# Power_Board_DCDC19V5.net
KiCad netlist of a schematic drawn in Altium Designer
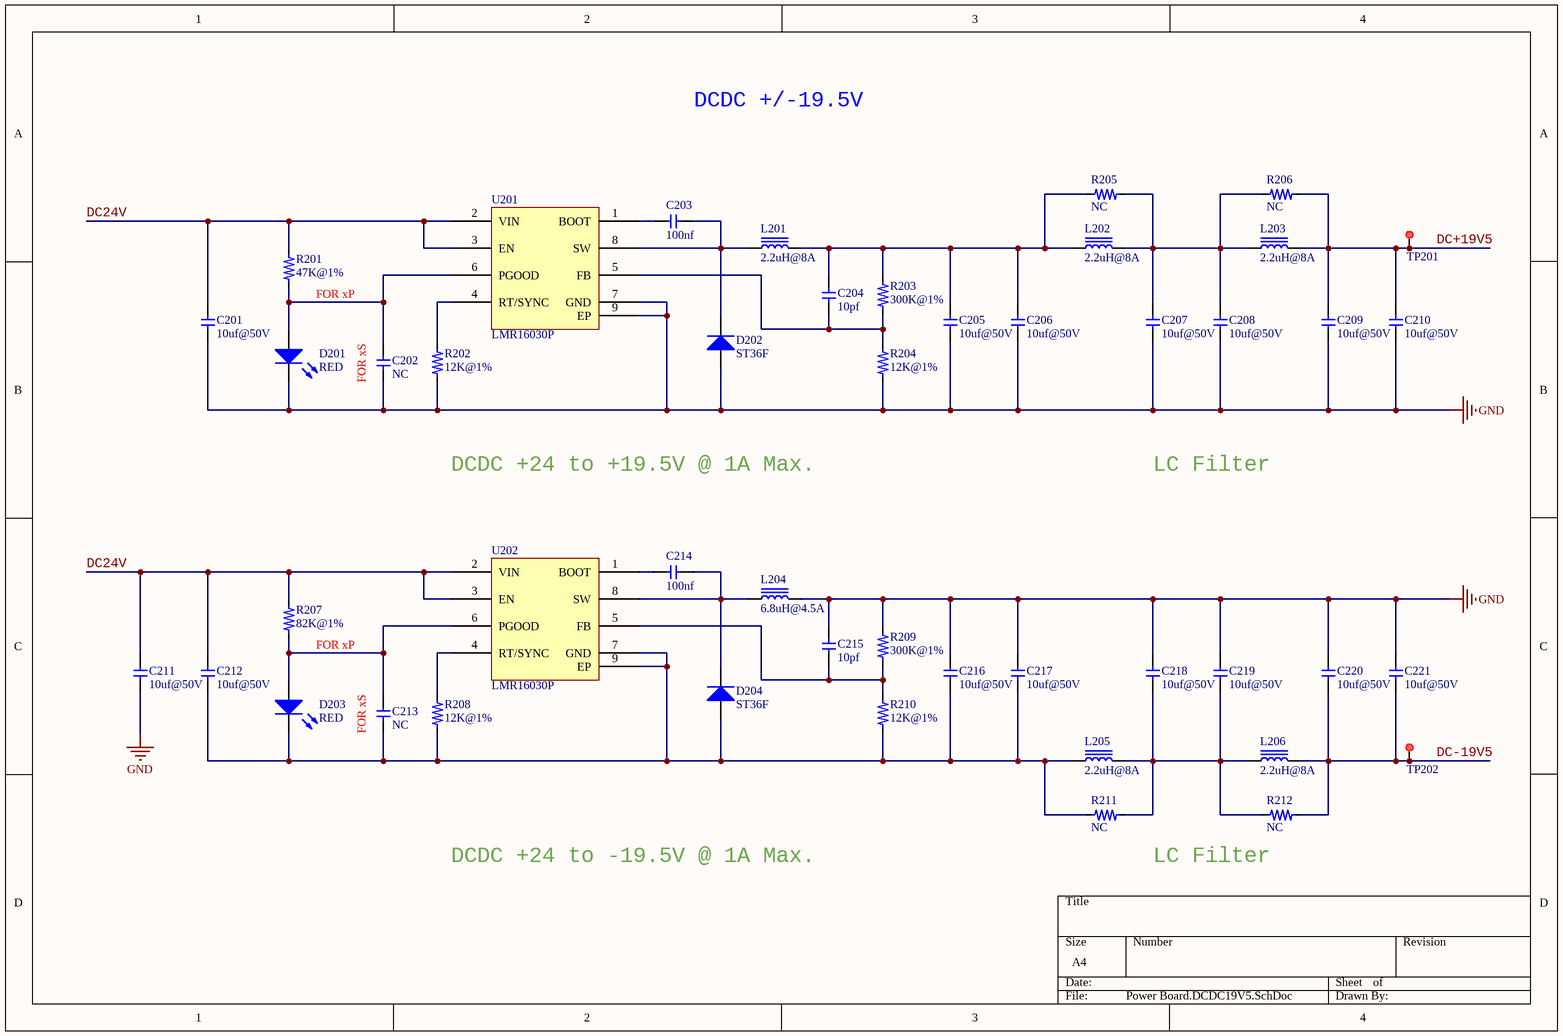
[diagram p0: Power Board.DCDC19V5.SchDoc]

(export (version "E")
  (design (tool "Eeschema 10.0.6"))
  (components
    (comp (ref "C201")
      (value "10uf@50V")
      (footprint "C1206")
      (fields (field (name "Comment") "Cap"))
      (libsource (lib "carrot_lib") (part "Cap"))
    )
    (comp (ref "C202")
      (value "NC")
      (footprint "C0603")
      (fields (field (name "Comment") "Cap"))
      (libsource (lib "carrot_lib") (part "Cap"))
    )
    (comp (ref "C203")
      (value "100nf")
      (footprint "C0603")
      (fields (field (name "Comment") "Cap"))
      (libsource (lib "carrot_lib") (part "Cap"))
    )
    (comp (ref "C204")
      (value "10pf")
      (footprint "C0603")
      (fields (field (name "Comment") "Cap"))
      (libsource (lib "carrot_lib") (part "Cap"))
    )
    (comp (ref "C205")
      (value "10uf@50V")
      (footprint "C1206")
      (fields (field (name "Comment") "Cap"))
      (libsource (lib "carrot_lib") (part "Cap"))
    )
    (comp (ref "C206")
      (value "10uf@50V")
      (footprint "C1206")
      (fields (field (name "Comment") "Cap"))
      (libsource (lib "carrot_lib") (part "Cap"))
    )
    (comp (ref "C207")
      (value "10uf@50V")
      (footprint "C1206")
      (fields (field (name "Comment") "Cap"))
      (libsource (lib "carrot_lib") (part "Cap"))
    )
    (comp (ref "C208")
      (value "10uf@50V")
      (footprint "C1206")
      (fields (field (name "Comment") "Cap"))
      (libsource (lib "carrot_lib") (part "Cap"))
    )
    (comp (ref "C209")
      (value "10uf@50V")
      (footprint "C1206")
      (fields (field (name "Comment") "Cap"))
      (libsource (lib "carrot_lib") (part "Cap"))
    )
    (comp (ref "C210")
      (value "10uf@50V")
      (footprint "C1206")
      (fields (field (name "Comment") "Cap"))
      (libsource (lib "carrot_lib") (part "Cap"))
    )
    (comp (ref "C211")
      (value "10uf@50V")
      (footprint "C1206")
      (fields (field (name "Comment") "Cap"))
      (libsource (lib "carrot_lib") (part "Cap"))
    )
    (comp (ref "C212")
      (value "10uf@50V")
      (footprint "C1206")
      (fields (field (name "Comment") "Cap"))
      (libsource (lib "carrot_lib") (part "Cap"))
    )
    (comp (ref "C213")
      (value "NC")
      (footprint "C0603")
      (fields (field (name "Comment") "Cap"))
      (libsource (lib "carrot_lib") (part "Cap"))
    )
    (comp (ref "C214")
      (value "100nf")
      (footprint "C0603")
      (fields (field (name "Comment") "Cap"))
      (libsource (lib "carrot_lib") (part "Cap"))
    )
    (comp (ref "C215")
      (value "10pf")
      (footprint "C0603")
      (fields (field (name "Comment") "Cap"))
      (libsource (lib "carrot_lib") (part "Cap"))
    )
    (comp (ref "C216")
      (value "10uf@50V")
      (footprint "C1206")
      (fields (field (name "Comment") "Cap"))
      (libsource (lib "carrot_lib") (part "Cap"))
    )
    (comp (ref "C217")
      (value "10uf@50V")
      (footprint "C1206")
      (fields (field (name "Comment") "Cap"))
      (libsource (lib "carrot_lib") (part "Cap"))
    )
    (comp (ref "C218")
      (value "10uf@50V")
      (footprint "C1206")
      (fields (field (name "Comment") "Cap"))
      (libsource (lib "carrot_lib") (part "Cap"))
    )
    (comp (ref "C219")
      (value "10uf@50V")
      (footprint "C1206")
      (fields (field (name "Comment") "Cap"))
      (libsource (lib "carrot_lib") (part "Cap"))
    )
    (comp (ref "C220")
      (value "10uf@50V")
      (footprint "C1206")
      (fields (field (name "Comment") "Cap"))
      (libsource (lib "carrot_lib") (part "Cap"))
    )
    (comp (ref "C221")
      (value "10uf@50V")
      (footprint "C1206")
      (fields (field (name "Comment") "Cap"))
      (libsource (lib "carrot_lib") (part "Cap"))
    )
    (comp (ref "D201")
      (value "RED")
      (footprint "LED0603")
      (fields (field (name "Comment") "LED"))
      (libsource (lib "carrot_lib") (part "LED"))
    )
    (comp (ref "D202")
      (value "ST36F")
      (footprint "DIODE-SMAF")
      (description "通用二极管")
      (fields (field (name "Comment") "Diode"))
      (libsource (lib "carrot_lib") (part "Diode"))
    )
    (comp (ref "D203")
      (value "RED")
      (footprint "LED0603")
      (fields (field (name "Comment") "LED"))
      (libsource (lib "carrot_lib") (part "LED"))
    )
    (comp (ref "D204")
      (value "ST36F")
      (footprint "DIODE-SMAF")
      (description "通用二极管")
      (fields (field (name "Comment") "Diode"))
      (libsource (lib "carrot_lib") (part "Diode"))
    )
    (comp (ref "L201")
      (value "2.2uH@8A")
      (footprint "L06063")
      (description "Magnetic-Core Inductor")
      (fields (field (name "Comment") "Inductor Iron"))
      (libsource (lib "carrot_lib") (part "Inductor Iron"))
    )
    (comp (ref "L202")
      (value "2.2uH@8A")
      (footprint "L06063")
      (description "Magnetic-Core Inductor")
      (fields (field (name "Comment") "Inductor Iron"))
      (libsource (lib "carrot_lib") (part "Inductor Iron"))
    )
    (comp (ref "L203")
      (value "2.2uH@8A")
      (footprint "L06063")
      (description "Magnetic-Core Inductor")
      (fields (field (name "Comment") "Inductor Iron"))
      (libsource (lib "carrot_lib") (part "Inductor Iron"))
    )
    (comp (ref "L204")
      (value "6.8uH@4.5A")
      (footprint "L06063")
      (description "Magnetic-Core Inductor")
      (fields (field (name "Comment") "Inductor Iron"))
      (libsource (lib "carrot_lib") (part "Inductor Iron"))
    )
    (comp (ref "L205")
      (value "2.2uH@8A")
      (footprint "L06063")
      (description "Magnetic-Core Inductor")
      (fields (field (name "Comment") "Inductor Iron"))
      (libsource (lib "carrot_lib") (part "Inductor Iron"))
    )
    (comp (ref "L206")
      (value "2.2uH@8A")
      (footprint "L06063")
      (description "Magnetic-Core Inductor")
      (fields (field (name "Comment") "Inductor Iron"))
      (libsource (lib "carrot_lib") (part "Inductor Iron"))
    )
    (comp (ref "R201")
      (value "47K@1%")
      (footprint "R0603")
      (description "电阻")
      (fields (field (name "Comment") "Res"))
      (libsource (lib "carrot_lib") (part "Res"))
    )
    (comp (ref "R202")
      (value "12K@1%")
      (footprint "R0603")
      (description "电阻")
      (fields (field (name "Comment") "Res"))
      (libsource (lib "carrot_lib") (part "Res"))
    )
    (comp (ref "R203")
      (value "300K@1%")
      (footprint "R0603")
      (description "电阻")
      (fields (field (name "Comment") "Res"))
      (libsource (lib "carrot_lib") (part "Res"))
    )
    (comp (ref "R204")
      (value "12K@1%")
      (footprint "R0603")
      (description "电阻")
      (fields (field (name "Comment") "Res"))
      (libsource (lib "carrot_lib") (part "Res"))
    )
    (comp (ref "R205")
      (value "NC")
      (footprint "R0805")
      (description "电阻")
      (fields (field (name "Comment") "Res"))
      (libsource (lib "carrot_lib") (part "Res"))
    )
    (comp (ref "R206")
      (value "NC")
      (footprint "R0805")
      (description "电阻")
      (fields (field (name "Comment") "Res"))
      (libsource (lib "carrot_lib") (part "Res"))
    )
    (comp (ref "R207")
      (value "82K@1%")
      (footprint "R0603")
      (description "电阻")
      (fields (field (name "Comment") "Res"))
      (libsource (lib "carrot_lib") (part "Res"))
    )
    (comp (ref "R208")
      (value "12K@1%")
      (footprint "R0603")
      (description "电阻")
      (fields (field (name "Comment") "Res"))
      (libsource (lib "carrot_lib") (part "Res"))
    )
    (comp (ref "R209")
      (value "300K@1%")
      (footprint "R0603")
      (description "电阻")
      (fields (field (name "Comment") "Res"))
      (libsource (lib "carrot_lib") (part "Res"))
    )
    (comp (ref "R210")
      (value "12K@1%")
      (footprint "R0603")
      (description "电阻")
      (fields (field (name "Comment") "Res"))
      (libsource (lib "carrot_lib") (part "Res"))
    )
    (comp (ref "R211")
      (value "NC")
      (footprint "R0805")
      (description "电阻")
      (fields (field (name "Comment") "Res"))
      (libsource (lib "carrot_lib") (part "Res"))
    )
    (comp (ref "R212")
      (value "NC")
      (footprint "R0805")
      (description "电阻")
      (fields (field (name "Comment") "Res"))
      (libsource (lib "carrot_lib") (part "Res"))
    )
    (comp (ref "TP201")
      (value "TestPoint")
      (footprint "TestPoint-THM1.0-L")
      (description "测试点")
      (libsource (lib "carrot_lib") (part "TestPoint"))
    )
    (comp (ref "TP202")
      (value "TestPoint")
      (footprint "TestPoint-THM1.0-L")
      (description "测试点")
      (libsource (lib "carrot_lib") (part "TestPoint"))
    )
    (comp (ref "U201")
      (value "LMR16030P")
      (footprint "LMR16030-SOIC8")
      (description "LMR16030 SIMPLE SWITCHER® 60-V, 3-A Step-Down Converter With 40-µA IQ")
      (libsource (lib "carrot_lib") (part "LMR16030P"))
    )
    (comp (ref "U202")
      (value "LMR16030P")
      (footprint "LMR16030-SOIC8")
      (description "LMR16030 SIMPLE SWITCHER® 60-V, 3-A Step-Down Converter With 40-µA IQ")
      (libsource (lib "carrot_lib") (part "LMR16030P"))
    )
  )
  (nets
    (net (code "1") (name "/DC+19V5") (class "Default")
      (node (ref "C209") (pin "2") (pinfunction "2_2") (pintype "passive"))
      (node (ref "C210") (pin "2") (pinfunction "2_2") (pintype "passive"))
      (node (ref "L203") (pin "2") (pinfunction "2_2") (pintype "passive"))
      (node (ref "R206") (pin "1") (pinfunction "1_1") (pintype "passive"))
      (node (ref "TP201") (pin "1") (pinfunction "1_1") (pintype "passive"))
    )
    (net (code "2") (name "/DC-19V5") (class "Default")
      (node (ref "C220") (pin "1") (pinfunction "1_1") (pintype "passive"))
      (node (ref "C221") (pin "1") (pinfunction "1_1") (pintype "passive"))
      (node (ref "L206") (pin "2") (pinfunction "2_2") (pintype "passive"))
      (node (ref "R212") (pin "1") (pinfunction "1_1") (pintype "passive"))
      (node (ref "TP202") (pin "1") (pinfunction "1_1") (pintype "passive"))
    )
    (net (code "3") (name "/DC24V") (class "Default")
      (node (ref "C201") (pin "2") (pinfunction "2_2") (pintype "passive"))
      (node (ref "C211") (pin "2") (pinfunction "2_2") (pintype "passive"))
      (node (ref "C212") (pin "2") (pinfunction "2_2") (pintype "passive"))
      (node (ref "R201") (pin "2") (pinfunction "2_2") (pintype "passive"))
      (node (ref "R207") (pin "2") (pinfunction "2_2") (pintype "passive"))
      (node (ref "U201") (pin "2") (pinfunction "VIN_2") (pintype "passive"))
      (node (ref "U201") (pin "3") (pinfunction "EN_3") (pintype "passive"))
      (node (ref "U202") (pin "2") (pinfunction "VIN_2") (pintype "passive"))
      (node (ref "U202") (pin "3") (pinfunction "EN_3") (pintype "passive"))
    )
    (net (code "4") (name "GND") (class "Default")
      (node (ref "C201") (pin "1") (pinfunction "1_1") (pintype "passive"))
      (node (ref "C202") (pin "1") (pinfunction "1_1") (pintype "passive"))
      (node (ref "C205") (pin "1") (pinfunction "1_1") (pintype "passive"))
      (node (ref "C206") (pin "1") (pinfunction "1_1") (pintype "passive"))
      (node (ref "C207") (pin "1") (pinfunction "1_1") (pintype "passive"))
      (node (ref "C208") (pin "1") (pinfunction "1_1") (pintype "passive"))
      (node (ref "C209") (pin "1") (pinfunction "1_1") (pintype "passive"))
      (node (ref "C210") (pin "1") (pinfunction "1_1") (pintype "passive"))
      (node (ref "C211") (pin "1") (pinfunction "1_1") (pintype "passive"))
      (node (ref "C215") (pin "1") (pinfunction "1_1") (pintype "passive"))
      (node (ref "C216") (pin "2") (pinfunction "2_2") (pintype "passive"))
      (node (ref "C217") (pin "2") (pinfunction "2_2") (pintype "passive"))
      (node (ref "C218") (pin "2") (pinfunction "2_2") (pintype "passive"))
      (node (ref "C219") (pin "2") (pinfunction "2_2") (pintype "passive"))
      (node (ref "C220") (pin "2") (pinfunction "2_2") (pintype "passive"))
      (node (ref "C221") (pin "2") (pinfunction "2_2") (pintype "passive"))
      (node (ref "D201") (pin "2") (pinfunction "K_2") (pintype "passive"))
      (node (ref "D202") (pin "1") (pinfunction "A_1") (pintype "passive"))
      (node (ref "L204") (pin "2") (pinfunction "2_2") (pintype "passive"))
      (node (ref "R202") (pin "1") (pinfunction "1_1") (pintype "passive"))
      (node (ref "R204") (pin "1") (pinfunction "1_1") (pintype "passive"))
      (node (ref "R209") (pin "2") (pinfunction "2_2") (pintype "passive"))
      (node (ref "U201") (pin "7") (pinfunction "GND_7") (pintype "passive"))
      (node (ref "U201") (pin "9") (pinfunction "EP_9") (pintype "passive"))
    )
    (net (code "5") (name "Net-(C204-Pad1)") (class "Default")
      (node (ref "C204") (pin "1") (pinfunction "1_1") (pintype "passive"))
      (node (ref "C205") (pin "2") (pinfunction "2_2") (pintype "passive"))
      (node (ref "C206") (pin "2") (pinfunction "2_2") (pintype "passive"))
      (node (ref "L201") (pin "2") (pinfunction "2_2") (pintype "passive"))
      (node (ref "L202") (pin "1") (pinfunction "1_1") (pintype "passive"))
      (node (ref "R203") (pin "2") (pinfunction "2_2") (pintype "passive"))
      (node (ref "R205") (pin "2") (pinfunction "2_2") (pintype "passive"))
    )
    (net (code "6") (name "Net-(C207-Pad2)") (class "Default")
      (node (ref "C207") (pin "2") (pinfunction "2_2") (pintype "passive"))
      (node (ref "C208") (pin "2") (pinfunction "2_2") (pintype "passive"))
      (node (ref "L202") (pin "2") (pinfunction "2_2") (pintype "passive"))
      (node (ref "L203") (pin "1") (pinfunction "1_1") (pintype "passive"))
      (node (ref "R205") (pin "1") (pinfunction "1_1") (pintype "passive"))
      (node (ref "R206") (pin "2") (pinfunction "2_2") (pintype "passive"))
    )
    (net (code "7") (name "Net-(C218-Pad1)") (class "Default")
      (node (ref "C218") (pin "1") (pinfunction "1_1") (pintype "passive"))
      (node (ref "C219") (pin "1") (pinfunction "1_1") (pintype "passive"))
      (node (ref "L205") (pin "2") (pinfunction "2_2") (pintype "passive"))
      (node (ref "L206") (pin "1") (pinfunction "1_1") (pintype "passive"))
      (node (ref "R211") (pin "1") (pinfunction "1_1") (pintype "passive"))
      (node (ref "R212") (pin "2") (pinfunction "2_2") (pintype "passive"))
    )
    (net (code "8") (name "Net-(D201-A)") (class "Default")
      (node (ref "C202") (pin "2") (pinfunction "2_2") (pintype "passive"))
      (node (ref "D201") (pin "1") (pinfunction "A_1") (pintype "passive"))
      (node (ref "R201") (pin "1") (pinfunction "1_1") (pintype "passive"))
      (node (ref "U201") (pin "6") (pinfunction "PGOOD_6") (pintype "passive"))
    )
    (net (code "9") (name "Net-(D202-K)") (class "Default")
      (node (ref "C203") (pin "1") (pinfunction "1_1") (pintype "passive"))
      (node (ref "D202") (pin "2") (pinfunction "K_2") (pintype "passive"))
      (node (ref "L201") (pin "1") (pinfunction "1_1") (pintype "passive"))
      (node (ref "U201") (pin "8") (pinfunction "SW_8") (pintype "passive"))
    )
    (net (code "10") (name "Net-(D203-A)") (class "Default")
      (node (ref "C213") (pin "2") (pinfunction "2_2") (pintype "passive"))
      (node (ref "D203") (pin "1") (pinfunction "A_1") (pintype "passive"))
      (node (ref "R207") (pin "1") (pinfunction "1_1") (pintype "passive"))
      (node (ref "U202") (pin "6") (pinfunction "PGOOD_6") (pintype "passive"))
    )
    (net (code "11") (name "Net-(D203-K)") (class "Default")
      (node (ref "C212") (pin "1") (pinfunction "1_1") (pintype "passive"))
      (node (ref "C213") (pin "1") (pinfunction "1_1") (pintype "passive"))
      (node (ref "C216") (pin "1") (pinfunction "1_1") (pintype "passive"))
      (node (ref "C217") (pin "1") (pinfunction "1_1") (pintype "passive"))
      (node (ref "D203") (pin "2") (pinfunction "K_2") (pintype "passive"))
      (node (ref "D204") (pin "1") (pinfunction "A_1") (pintype "passive"))
      (node (ref "L205") (pin "1") (pinfunction "1_1") (pintype "passive"))
      (node (ref "R208") (pin "1") (pinfunction "1_1") (pintype "passive"))
      (node (ref "R210") (pin "1") (pinfunction "1_1") (pintype "passive"))
      (node (ref "R211") (pin "2") (pinfunction "2_2") (pintype "passive"))
      (node (ref "U202") (pin "7") (pinfunction "GND_7") (pintype "passive"))
      (node (ref "U202") (pin "9") (pinfunction "EP_9") (pintype "passive"))
    )
    (net (code "12") (name "Net-(D204-K)") (class "Default")
      (node (ref "C214") (pin "1") (pinfunction "1_1") (pintype "passive"))
      (node (ref "D204") (pin "2") (pinfunction "K_2") (pintype "passive"))
      (node (ref "L204") (pin "1") (pinfunction "1_1") (pintype "passive"))
      (node (ref "U202") (pin "8") (pinfunction "SW_8") (pintype "passive"))
    )
    (net (code "13") (name "Net-(U201-BOOT)") (class "Default")
      (node (ref "C203") (pin "2") (pinfunction "2_2") (pintype "passive"))
      (node (ref "U201") (pin "1") (pinfunction "BOOT_1") (pintype "passive"))
    )
    (net (code "14") (name "Net-(U201-FB)") (class "Default")
      (node (ref "C204") (pin "2") (pinfunction "2_2") (pintype "passive"))
      (node (ref "R203") (pin "1") (pinfunction "1_1") (pintype "passive"))
      (node (ref "R204") (pin "2") (pinfunction "2_2") (pintype "passive"))
      (node (ref "U201") (pin "5") (pinfunction "FB_5") (pintype "passive"))
    )
    (net (code "15") (name "Net-(U201-RT{slash}SYNC)") (class "Default")
      (node (ref "R202") (pin "2") (pinfunction "2_2") (pintype "passive"))
      (node (ref "U201") (pin "4") (pinfunction "RT/SYNC_4") (pintype "passive"))
    )
    (net (code "16") (name "Net-(U202-BOOT)") (class "Default")
      (node (ref "C214") (pin "2") (pinfunction "2_2") (pintype "passive"))
      (node (ref "U202") (pin "1") (pinfunction "BOOT_1") (pintype "passive"))
    )
    (net (code "17") (name "Net-(U202-FB)") (class "Default")
      (node (ref "C215") (pin "2") (pinfunction "2_2") (pintype "passive"))
      (node (ref "R209") (pin "1") (pinfunction "1_1") (pintype "passive"))
      (node (ref "R210") (pin "2") (pinfunction "2_2") (pintype "passive"))
      (node (ref "U202") (pin "5") (pinfunction "FB_5") (pintype "passive"))
    )
    (net (code "18") (name "Net-(U202-RT{slash}SYNC)") (class "Default")
      (node (ref "R208") (pin "2") (pinfunction "2_2") (pintype "passive"))
      (node (ref "U202") (pin "4") (pinfunction "RT/SYNC_4") (pintype "passive"))
    )
  )
)
